# FSI6CAN.net
KiCad netlist of a schematic drawn in EAGLE
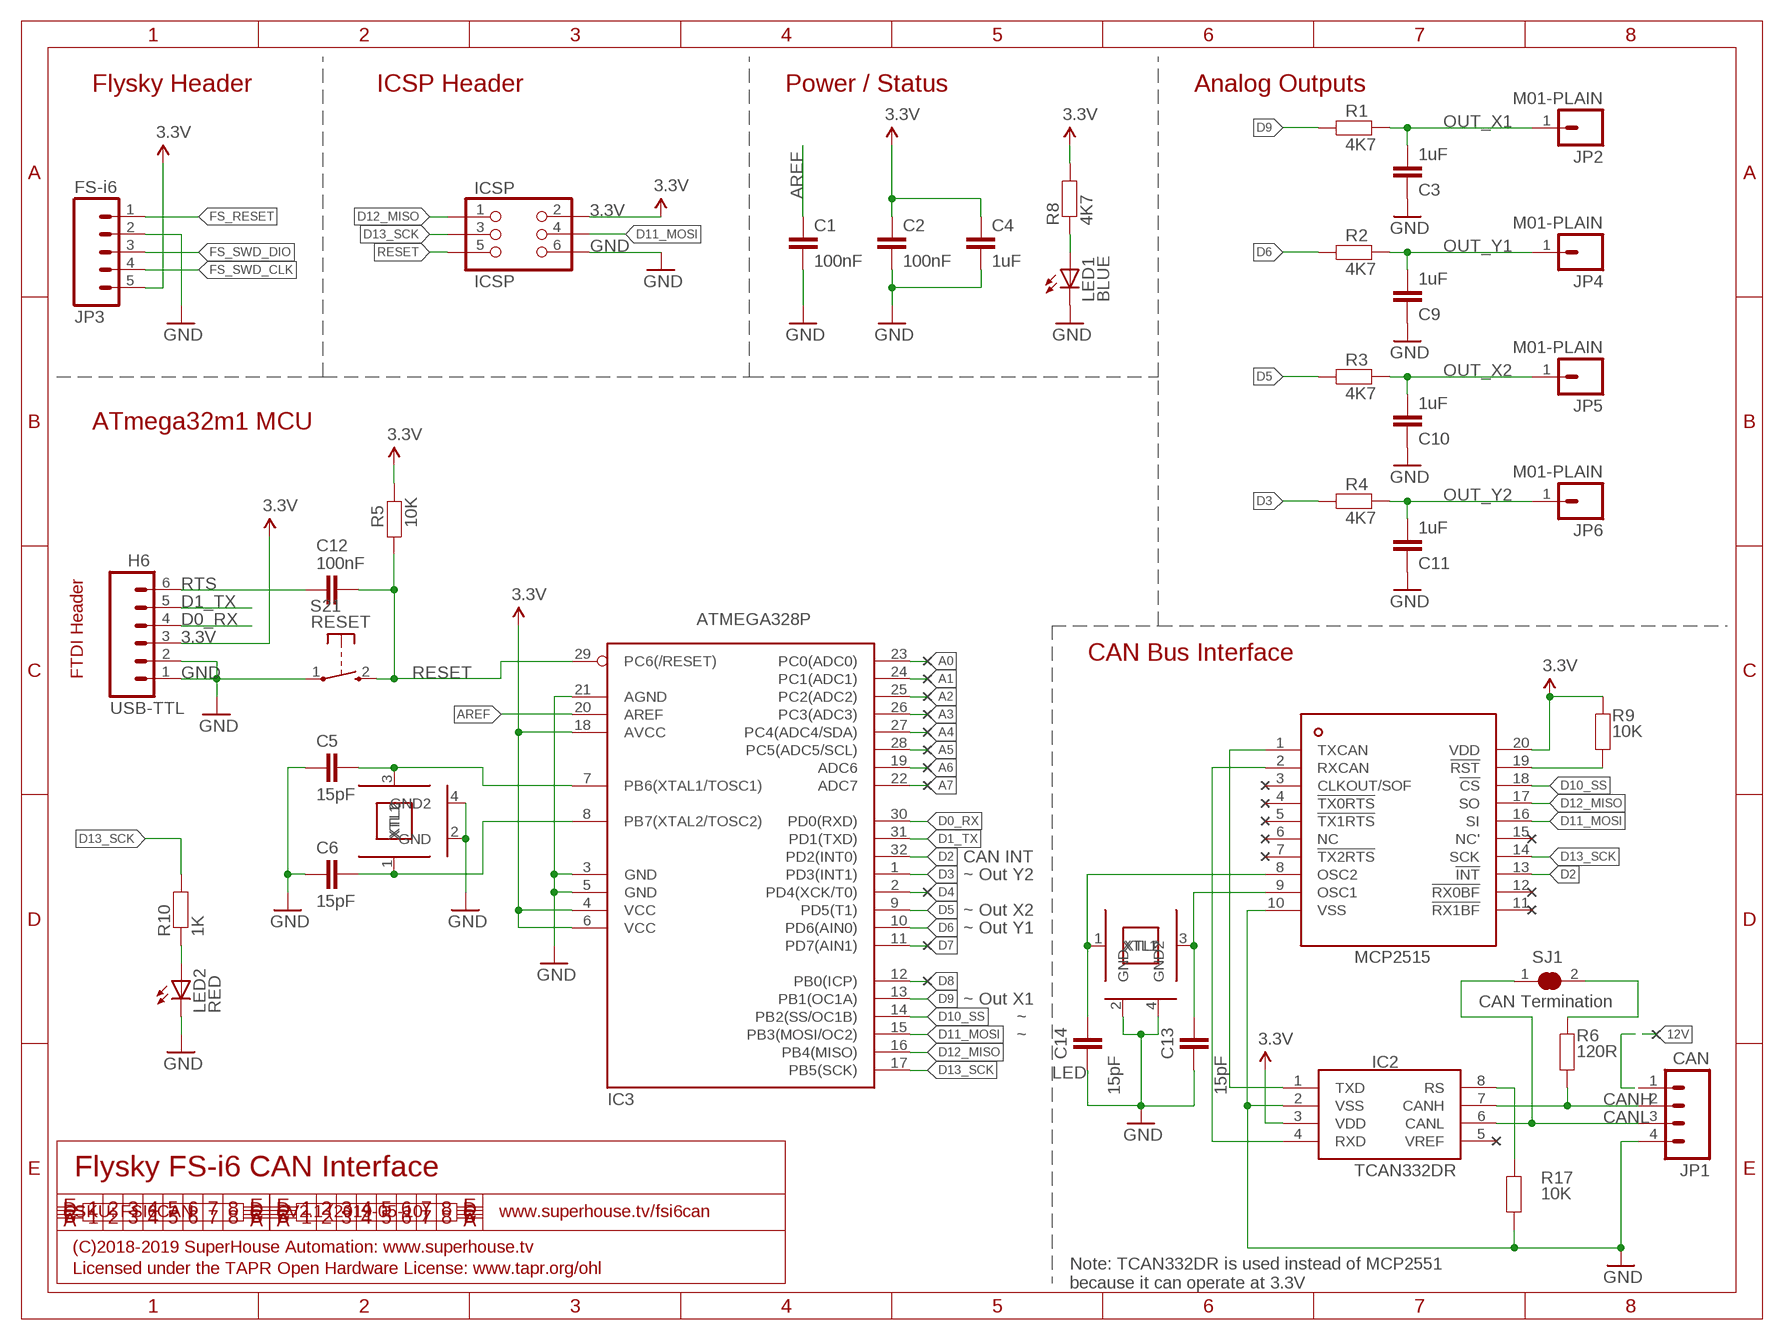
[diagram p0: schematic, sheet 1]

(export (version "E")
  (design (tool "Eeschema 10.0.6"))
  (components
    (comp (ref "C1")
      (value "100nF")
      (footprint "eagle-import:C0603")
      (libsource (lib "eagle-import") (part "CAP0603"))
    )
    (comp (ref "C2")
      (value "100nF")
      (footprint "eagle-import:C0603")
      (libsource (lib "eagle-import") (part "CAP0603"))
    )
    (comp (ref "C3")
      (value "1uF")
      (footprint "eagle-import:C0603")
      (libsource (lib "eagle-import") (part "CAP0603"))
    )
    (comp (ref "C4")
      (value "1uF")
      (footprint "eagle-import:C0603")
      (libsource (lib "eagle-import") (part "CAP0603"))
    )
    (comp (ref "C5")
      (value "15pF")
      (footprint "eagle-import:C0603")
      (libsource (lib "eagle-import") (part "CAP0603"))
    )
    (comp (ref "C6")
      (value "15pF")
      (footprint "eagle-import:C0603")
      (libsource (lib "eagle-import") (part "CAP0603"))
    )
    (comp (ref "C9")
      (value "1uF")
      (footprint "eagle-import:C0603")
      (libsource (lib "eagle-import") (part "CAP0603"))
    )
    (comp (ref "C10")
      (value "1uF")
      (footprint "eagle-import:C0603")
      (libsource (lib "eagle-import") (part "CAP0603"))
    )
    (comp (ref "C11")
      (value "1uF")
      (footprint "eagle-import:C0603")
      (libsource (lib "eagle-import") (part "CAP0603"))
    )
    (comp (ref "C12")
      (value "100nF")
      (footprint "eagle-import:C0603")
      (libsource (lib "eagle-import") (part "CAP0603"))
    )
    (comp (ref "C13")
      (value "15pF")
      (footprint "eagle-import:C0603")
      (libsource (lib "eagle-import") (part "CAP0603"))
    )
    (comp (ref "C14")
      (value "15pF")
      (footprint "eagle-import:C0603")
      (libsource (lib "eagle-import") (part "CAP0603"))
    )
    (comp (ref "H6")
      (value "USB-TTL")
      (footprint "eagle-import:1X06-P-RA")
      (libsource (lib "eagle-import") (part "M06-PIN-RIGHTANGLE"))
    )
    (comp (ref "IC2")
      (value "TCAN332DR")
      (footprint "eagle-import:SO08")
      (libsource (lib "eagle-import") (part "MCP2551"))
    )
    (comp (ref "IC3")
      (value "ATMEGA328P")
      (footprint "eagle-import:TQFP32-08")
      (libsource (lib "eagle-import") (part "ATMEGA8-AI"))
    )
    (comp (ref "IC4")
      (value "MCP2515")
      (footprint "eagle-import:TSSOP20")
      (libsource (lib "eagle-import") (part "MCP2515"))
    )
    (comp (ref "ICSP")
      (value "ICSP")
      (footprint "eagle-import:2X03-ICSP")
      (libsource (lib "eagle-import") (part "ICSP-PIN"))
    )
    (comp (ref "JP1")
      (value "CAN")
      (footprint "eagle-import:1X04-P")
      (libsource (lib "eagle-import") (part "M04-PIN"))
    )
    (comp (ref "JP2")
      (value "M01-PLAIN")
      (footprint "eagle-import:1X01")
      (libsource (lib "eagle-import") (part "M01-PLAIN"))
    )
    (comp (ref "JP3")
      (value "FS-i6")
      (footprint "eagle-import:1X05")
      (libsource (lib "eagle-import") (part "M05PTH"))
    )
    (comp (ref "JP4")
      (value "M01-PLAIN")
      (footprint "eagle-import:1X01")
      (libsource (lib "eagle-import") (part "M01-PLAIN"))
    )
    (comp (ref "JP5")
      (value "M01-PLAIN")
      (footprint "eagle-import:1X01")
      (libsource (lib "eagle-import") (part "M01-PLAIN"))
    )
    (comp (ref "JP6")
      (value "M01-PLAIN")
      (footprint "eagle-import:1X01")
      (libsource (lib "eagle-import") (part "M01-PLAIN"))
    )
    (comp (ref "LED1")
      (value "BLUE")
      (footprint "eagle-import:LED-0603")
      (libsource (lib "eagle-import") (part "LED0603"))
    )
    (comp (ref "LED2")
      (value "RED")
      (footprint "eagle-import:LED-0603")
      (libsource (lib "eagle-import") (part "LED0603"))
    )
    (comp (ref "R1")
      (value "4K7")
      (footprint "eagle-import:R0603")
      (libsource (lib "eagle-import") (part "RESISTOR0603"))
    )
    (comp (ref "R2")
      (value "4K7")
      (footprint "eagle-import:R0603")
      (libsource (lib "eagle-import") (part "RESISTOR0603"))
    )
    (comp (ref "R3")
      (value "4K7")
      (footprint "eagle-import:R0603")
      (libsource (lib "eagle-import") (part "RESISTOR0603"))
    )
    (comp (ref "R4")
      (value "4K7")
      (footprint "eagle-import:R0603")
      (libsource (lib "eagle-import") (part "RESISTOR0603"))
    )
    (comp (ref "R5")
      (value "10K")
      (footprint "eagle-import:R0603")
      (libsource (lib "eagle-import") (part "RESISTOR0603"))
    )
    (comp (ref "R6")
      (value "120R")
      (footprint "eagle-import:R0603")
      (libsource (lib "eagle-import") (part "RESISTOR0603"))
    )
    (comp (ref "R8")
      (value "4K7")
      (footprint "eagle-import:R0603")
      (libsource (lib "eagle-import") (part "RESISTOR0603"))
    )
    (comp (ref "R9")
      (value "10K")
      (footprint "eagle-import:R0603")
      (libsource (lib "eagle-import") (part "RESISTOR0603"))
    )
    (comp (ref "R10")
      (value "1K")
      (footprint "eagle-import:R0603")
      (libsource (lib "eagle-import") (part "RESISTOR0603"))
    )
    (comp (ref "R17")
      (value "10K")
      (footprint "eagle-import:R0603")
      (libsource (lib "eagle-import") (part "RESISTOR0603"))
    )
    (comp (ref "S21")
      (value "RESET")
      (footprint "eagle-import:TACTILE_SMT_3X4X2")
      (libsource (lib "eagle-import") (part "TAC_SWITCH_2PINSMT"))
    )
    (comp (ref "SJ1")
      (value "CAN Termination")
      (footprint "eagle-import:SJC")
      (libsource (lib "eagle-import") (part "SJC-NORMAL"))
    )
    (comp (ref "XTL1")
      (value "8MHz")
      (footprint "eagle-import:CRYSTAL-SMD-3X2")
      (libsource (lib "eagle-import") (part "CRYSTAL-GND3X2"))
    )
    (comp (ref "XTL3")
      (value "16MHz")
      (footprint "eagle-import:CRYSTAL-SMD-3X2")
      (libsource (lib "eagle-import") (part "CRYSTAL-GND3X2"))
    )
  )
  (nets
    (net (code "1") (name "/CANH") (class "Default")
      (node (ref "IC2") (pin "7") (pinfunction "CANH_7") (pintype "bidirectional"))
      (node (ref "JP1") (pin "2") (pinfunction "2_2") (pintype "passive"))
      (node (ref "R6") (pin "1") (pinfunction "1_1") (pintype "passive"))
    )
    (net (code "2") (name "/CANL") (class "Default")
      (node (ref "IC2") (pin "6") (pinfunction "CANL_6") (pintype "bidirectional"))
      (node (ref "JP1") (pin "3") (pinfunction "3_3") (pintype "passive"))
      (node (ref "SJ1") (pin "1") (pinfunction "1_1") (pintype "passive"))
    )
    (net (code "3") (name "/OUT_X1") (class "Default")
      (node (ref "C3") (pin "1") (pinfunction "1_1") (pintype "passive"))
      (node (ref "JP2") (pin "1") (pinfunction "1_1") (pintype "passive"))
      (node (ref "R1") (pin "2") (pinfunction "2_2") (pintype "passive"))
    )
    (net (code "4") (name "/OUT_X2") (class "Default")
      (node (ref "C10") (pin "1") (pinfunction "1_1") (pintype "passive"))
      (node (ref "JP5") (pin "1") (pinfunction "1_1") (pintype "passive"))
      (node (ref "R3") (pin "2") (pinfunction "2_2") (pintype "passive"))
    )
    (net (code "5") (name "/OUT_Y1") (class "Default")
      (node (ref "C9") (pin "1") (pinfunction "1_1") (pintype "passive"))
      (node (ref "JP4") (pin "1") (pinfunction "1_1") (pintype "passive"))
      (node (ref "R2") (pin "2") (pinfunction "2_2") (pintype "passive"))
    )
    (net (code "6") (name "/OUT_Y2") (class "Default")
      (node (ref "C11") (pin "1") (pinfunction "1_1") (pintype "passive"))
      (node (ref "JP6") (pin "1") (pinfunction "1_1") (pintype "passive"))
      (node (ref "R4") (pin "2") (pinfunction "2_2") (pintype "passive"))
    )
    (net (code "7") (name "/RTS") (class "Default")
      (node (ref "C12") (pin "1") (pinfunction "1_1") (pintype "passive"))
      (node (ref "H6") (pin "6") (pinfunction "6_6") (pintype "passive"))
    )
    (net (code "8") (name "3.3V") (class "Default")
      (node (ref "C2") (pin "1") (pinfunction "1_1") (pintype "passive"))
      (node (ref "C4") (pin "1") (pinfunction "1_1") (pintype "passive"))
      (node (ref "H6") (pin "3") (pinfunction "3_3") (pintype "passive"))
      (node (ref "IC2") (pin "3") (pinfunction "VDD_3") (pintype "bidirectional"))
      (node (ref "IC3") (pin "18") (pinfunction "AVCC_18") (pintype "bidirectional"))
      (node (ref "IC3") (pin "4") (pinfunction "VCC_4") (pintype "bidirectional"))
      (node (ref "IC3") (pin "6") (pinfunction "VCC_6") (pintype "bidirectional"))
      (node (ref "IC4") (pin "20") (pinfunction "VDD_20") (pintype "bidirectional"))
      (node (ref "ICSP") (pin "2") (pinfunction "2_2") (pintype "passive"))
      (node (ref "JP3") (pin "5") (pinfunction "5_5") (pintype "passive"))
      (node (ref "R5") (pin "1") (pinfunction "1_1") (pintype "passive"))
      (node (ref "R8") (pin "2") (pinfunction "2_2") (pintype "passive"))
      (node (ref "R9") (pin "2") (pinfunction "2_2") (pintype "passive"))
    )
    (net (code "9") (name "12V") (class "Default")
      (node (ref "JP1") (pin "1") (pinfunction "1_1") (pintype "passive"))
    )
    (net (code "10") (name "A0") (class "Default")
      (node (ref "IC3") (pin "23") (pinfunction "PC0(ADC0)_23") (pintype "bidirectional"))
    )
    (net (code "11") (name "A1") (class "Default")
      (node (ref "IC3") (pin "24") (pinfunction "PC1(ADC1)_24") (pintype "bidirectional"))
    )
    (net (code "12") (name "A2") (class "Default")
      (node (ref "IC3") (pin "25") (pinfunction "PC2(ADC2)_25") (pintype "bidirectional"))
    )
    (net (code "13") (name "A3") (class "Default")
      (node (ref "IC3") (pin "26") (pinfunction "PC3(ADC3)_26") (pintype "bidirectional"))
    )
    (net (code "14") (name "A4") (class "Default")
      (node (ref "IC3") (pin "27") (pinfunction "PC4(ADC4/SDA)_27") (pintype "bidirectional"))
    )
    (net (code "15") (name "A5") (class "Default")
      (node (ref "IC3") (pin "28") (pinfunction "PC5(ADC5/SCL)_28") (pintype "bidirectional"))
    )
    (net (code "16") (name "A6") (class "Default")
      (node (ref "IC3") (pin "19") (pinfunction "ADC6_19") (pintype "bidirectional"))
    )
    (net (code "17") (name "A7") (class "Default")
      (node (ref "IC3") (pin "22") (pinfunction "ADC7_22") (pintype "bidirectional"))
    )
    (net (code "18") (name "AREF") (class "Default")
      (node (ref "C1") (pin "1") (pinfunction "1_1") (pintype "passive"))
      (node (ref "IC3") (pin "20") (pinfunction "AREF_20") (pintype "bidirectional"))
    )
    (net (code "19") (name "D0_RX") (class "Default")
      (node (ref "H6") (pin "4") (pinfunction "4_4") (pintype "passive"))
      (node (ref "IC3") (pin "30") (pinfunction "PD0(RXD)_30") (pintype "bidirectional"))
    )
    (net (code "20") (name "D1_TX") (class "Default")
      (node (ref "H6") (pin "5") (pinfunction "5_5") (pintype "passive"))
      (node (ref "IC3") (pin "31") (pinfunction "PD1(TXD)_31") (pintype "bidirectional"))
    )
    (net (code "21") (name "D2") (class "Default")
      (node (ref "IC3") (pin "32") (pinfunction "PD2(INT0)_32") (pintype "bidirectional"))
      (node (ref "IC4") (pin "13") (pinfunction "~{INT}_13") (pintype "bidirectional"))
    )
    (net (code "22") (name "D3") (class "Default")
      (node (ref "IC3") (pin "1") (pinfunction "PD3(INT1)_1") (pintype "bidirectional"))
      (node (ref "R4") (pin "1") (pinfunction "1_1") (pintype "passive"))
    )
    (net (code "23") (name "D4") (class "Default")
      (node (ref "IC3") (pin "2") (pinfunction "PD4(XCK/T0)_2") (pintype "bidirectional"))
    )
    (net (code "24") (name "D5") (class "Default")
      (node (ref "IC3") (pin "9") (pinfunction "PD5(T1)_9") (pintype "bidirectional"))
      (node (ref "R3") (pin "1") (pinfunction "1_1") (pintype "passive"))
    )
    (net (code "25") (name "D6") (class "Default")
      (node (ref "IC3") (pin "10") (pinfunction "PD6(AIN0)_10") (pintype "bidirectional"))
      (node (ref "R2") (pin "1") (pinfunction "1_1") (pintype "passive"))
    )
    (net (code "26") (name "D7") (class "Default")
      (node (ref "IC3") (pin "11") (pinfunction "PD7(AIN1)_11") (pintype "bidirectional"))
    )
    (net (code "27") (name "D8") (class "Default")
      (node (ref "IC3") (pin "12") (pinfunction "PB0(ICP)_12") (pintype "bidirectional"))
    )
    (net (code "28") (name "D9") (class "Default")
      (node (ref "IC3") (pin "13") (pinfunction "PB1(OC1A)_13") (pintype "bidirectional"))
      (node (ref "R1") (pin "1") (pinfunction "1_1") (pintype "passive"))
    )
    (net (code "29") (name "D10_SS") (class "Default")
      (node (ref "IC3") (pin "14") (pinfunction "PB2(SS/OC1B)_14") (pintype "bidirectional"))
      (node (ref "IC4") (pin "18") (pinfunction "~{CS}_18") (pintype "bidirectional"))
    )
    (net (code "30") (name "D11_MOSI") (class "Default")
      (node (ref "IC3") (pin "15") (pinfunction "PB3(MOSI/OC2)_15") (pintype "bidirectional"))
      (node (ref "IC4") (pin "16") (pinfunction "SI_16") (pintype "bidirectional"))
      (node (ref "ICSP") (pin "4") (pinfunction "4_4") (pintype "passive"))
    )
    (net (code "31") (name "D12_MISO") (class "Default")
      (node (ref "IC3") (pin "16") (pinfunction "PB4(MISO)_16") (pintype "bidirectional"))
      (node (ref "IC4") (pin "17") (pinfunction "SO_17") (pintype "bidirectional"))
      (node (ref "ICSP") (pin "1") (pinfunction "1_1") (pintype "passive"))
    )
    (net (code "32") (name "D13_SCK") (class "Default")
      (node (ref "IC3") (pin "17") (pinfunction "PB5(SCK)_17") (pintype "bidirectional"))
      (node (ref "IC4") (pin "14") (pinfunction "SCK_14") (pintype "bidirectional"))
      (node (ref "ICSP") (pin "3") (pinfunction "3_3") (pintype "passive"))
      (node (ref "R10") (pin "2") (pinfunction "2_2") (pintype "passive"))
    )
    (net (code "33") (name "FS_RESET") (class "Default")
      (node (ref "JP3") (pin "1") (pinfunction "1_1") (pintype "passive"))
    )
    (net (code "34") (name "FS_SWD_CLK") (class "Default")
      (node (ref "JP3") (pin "4") (pinfunction "4_4") (pintype "passive"))
    )
    (net (code "35") (name "FS_SWD_DIO") (class "Default")
      (node (ref "JP3") (pin "3") (pinfunction "3_3") (pintype "passive"))
    )
    (net (code "36") (name "GND") (class "Default")
      (node (ref "C1") (pin "2") (pinfunction "2_2") (pintype "passive"))
      (node (ref "C10") (pin "2") (pinfunction "2_2") (pintype "passive"))
      (node (ref "C11") (pin "2") (pinfunction "2_2") (pintype "passive"))
      (node (ref "C13") (pin "1") (pinfunction "1_1") (pintype "passive"))
      (node (ref "C14") (pin "1") (pinfunction "1_1") (pintype "passive"))
      (node (ref "C2") (pin "2") (pinfunction "2_2") (pintype "passive"))
      (node (ref "C3") (pin "2") (pinfunction "2_2") (pintype "passive"))
      (node (ref "C4") (pin "2") (pinfunction "2_2") (pintype "passive"))
      (node (ref "C5") (pin "1") (pinfunction "1_1") (pintype "passive"))
      (node (ref "C6") (pin "1") (pinfunction "1_1") (pintype "passive"))
      (node (ref "C9") (pin "2") (pinfunction "2_2") (pintype "passive"))
      (node (ref "H6") (pin "1") (pinfunction "1_1") (pintype "passive"))
      (node (ref "H6") (pin "2") (pinfunction "2_2") (pintype "passive"))
      (node (ref "IC2") (pin "2") (pinfunction "VSS_2") (pintype "bidirectional"))
      (node (ref "IC3") (pin "21") (pinfunction "AGND_21") (pintype "bidirectional"))
      (node (ref "IC3") (pin "3") (pinfunction "GND_3") (pintype "bidirectional"))
      (node (ref "IC3") (pin "5") (pinfunction "GND_5") (pintype "bidirectional"))
      (node (ref "IC4") (pin "10") (pinfunction "VSS_10") (pintype "bidirectional"))
      (node (ref "ICSP") (pin "6") (pinfunction "6_6") (pintype "passive"))
      (node (ref "JP1") (pin "4") (pinfunction "4_4") (pintype "passive"))
      (node (ref "JP3") (pin "2") (pinfunction "2_2") (pintype "passive"))
      (node (ref "LED1") (pin "C") (pinfunction "C_C") (pintype "passive"))
      (node (ref "LED2") (pin "C") (pinfunction "C_C") (pintype "passive"))
      (node (ref "R17") (pin "1") (pinfunction "1_1") (pintype "passive"))
      (node (ref "S21") (pin "1") (pinfunction "P_1") (pintype "passive"))
      (node (ref "XTL1") (pin "2") (pinfunction "GND_2") (pintype "bidirectional"))
      (node (ref "XTL1") (pin "4") (pinfunction "GND2_4") (pintype "bidirectional"))
      (node (ref "XTL3") (pin "2") (pinfunction "GND_2") (pintype "bidirectional"))
      (node (ref "XTL3") (pin "4") (pinfunction "GND2_4") (pintype "bidirectional"))
    )
    (net (code "37") (name "Net-(IC2-RS)") (class "Default")
      (node (ref "IC2") (pin "8") (pinfunction "RS_8") (pintype "bidirectional"))
      (node (ref "R17") (pin "2") (pinfunction "2_2") (pintype "passive"))
    )
    (net (code "38") (name "Net-(IC2-RXD)") (class "Default")
      (node (ref "IC2") (pin "4") (pinfunction "RXD_4") (pintype "bidirectional"))
      (node (ref "IC4") (pin "2") (pinfunction "RXCAN_2") (pintype "bidirectional"))
    )
    (net (code "39") (name "Net-(IC2-TXD)") (class "Default")
      (node (ref "IC2") (pin "1") (pinfunction "TXD_1") (pintype "bidirectional"))
      (node (ref "IC4") (pin "1") (pinfunction "TXCAN_1") (pintype "bidirectional"))
    )
    (net (code "40") (name "Net-(IC3-PB6(XTAL1{slash}TOSC1))") (class "Default")
      (node (ref "C5") (pin "2") (pinfunction "2_2") (pintype "passive"))
      (node (ref "IC3") (pin "7") (pinfunction "PB6(XTAL1/TOSC1)_7") (pintype "bidirectional"))
      (node (ref "XTL1") (pin "3") (pinfunction "XTL2_3") (pintype "bidirectional"))
    )
    (net (code "41") (name "Net-(IC3-PB7(XTAL2{slash}TOSC2))") (class "Default")
      (node (ref "C6") (pin "2") (pinfunction "2_2") (pintype "passive"))
      (node (ref "IC3") (pin "8") (pinfunction "PB7(XTAL2/TOSC2)_8") (pintype "bidirectional"))
      (node (ref "XTL1") (pin "1") (pinfunction "XTL1_1") (pintype "bidirectional"))
    )
    (net (code "42") (name "Net-(IC4-OSC1)") (class "Default")
      (node (ref "C13") (pin "2") (pinfunction "2_2") (pintype "passive"))
      (node (ref "IC4") (pin "9") (pinfunction "OSC1_9") (pintype "bidirectional"))
      (node (ref "XTL3") (pin "3") (pinfunction "XTL2_3") (pintype "bidirectional"))
    )
    (net (code "43") (name "Net-(IC4-OSC2)") (class "Default")
      (node (ref "C14") (pin "2") (pinfunction "2_2") (pintype "passive"))
      (node (ref "IC4") (pin "8") (pinfunction "OSC2_8") (pintype "bidirectional"))
      (node (ref "XTL3") (pin "1") (pinfunction "XTL1_1") (pintype "bidirectional"))
    )
    (net (code "44") (name "Net-(IC4-~{RST})") (class "Default")
      (node (ref "IC4") (pin "19") (pinfunction "~{RST}_19") (pintype "bidirectional"))
      (node (ref "R9") (pin "1") (pinfunction "1_1") (pintype "passive"))
    )
    (net (code "45") (name "Net-(LED1-PadA)") (class "Default")
      (node (ref "LED1") (pin "A") (pinfunction "A_A") (pintype "passive"))
      (node (ref "R8") (pin "1") (pinfunction "1_1") (pintype "passive"))
    )
    (net (code "46") (name "Net-(LED2-PadA)") (class "Default")
      (node (ref "LED2") (pin "A") (pinfunction "A_A") (pintype "passive"))
      (node (ref "R10") (pin "1") (pinfunction "1_1") (pintype "passive"))
    )
    (net (code "47") (name "Net-(R6-Pad2)") (class "Default")
      (node (ref "R6") (pin "2") (pinfunction "2_2") (pintype "passive"))
      (node (ref "SJ1") (pin "2") (pinfunction "2_2") (pintype "passive"))
    )
    (net (code "48") (name "RESET") (class "Default")
      (node (ref "C12") (pin "2") (pinfunction "2_2") (pintype "passive"))
      (node (ref "IC3") (pin "29") (pinfunction "PC6(/RESET)_29") (pintype "bidirectional"))
      (node (ref "ICSP") (pin "5") (pinfunction "5_5") (pintype "passive"))
      (node (ref "R5") (pin "2") (pinfunction "2_2") (pintype "passive"))
      (node (ref "S21") (pin "2") (pinfunction "S_2") (pintype "passive"))
    )
    (net (code "49") (name "unconnected-(IC2-VREF-Pad5)") (class "Default")
      (node (ref "IC2") (pin "5") (pinfunction "VREF_5") (pintype "bidirectional"))
    )
    (net (code "50") (name "unconnected-(IC4-CLKOUT{slash}SOF-Pad3)") (class "Default")
      (node (ref "IC4") (pin "3") (pinfunction "CLKOUT/SOF_3") (pintype "bidirectional"))
    )
    (net (code "51") (name "unconnected-(IC4-NC'-Pad15)") (class "Default")
      (node (ref "IC4") (pin "15") (pinfunction "NC'_15") (pintype "bidirectional"))
    )
    (net (code "52") (name "unconnected-(IC4-NC-Pad6)") (class "Default")
      (node (ref "IC4") (pin "6") (pinfunction "NC_6") (pintype "bidirectional"))
    )
    (net (code "53") (name "unconnected-(IC4-~{RX0BF}-Pad12)") (class "Default")
      (node (ref "IC4") (pin "12") (pinfunction "~{RX0BF}_12") (pintype "bidirectional"))
    )
    (net (code "54") (name "unconnected-(IC4-~{RX1BF}-Pad11)") (class "Default")
      (node (ref "IC4") (pin "11") (pinfunction "~{RX1BF}_11") (pintype "bidirectional"))
    )
    (net (code "55") (name "unconnected-(IC4-~{TX0RTS}-Pad4)") (class "Default")
      (node (ref "IC4") (pin "4") (pinfunction "~{TX0RTS}_4") (pintype "bidirectional"))
    )
    (net (code "56") (name "unconnected-(IC4-~{TX1RTS}-Pad5)") (class "Default")
      (node (ref "IC4") (pin "5") (pinfunction "~{TX1RTS}_5") (pintype "bidirectional"))
    )
    (net (code "57") (name "unconnected-(IC4-~{TX2RTS}-Pad7)") (class "Default")
      (node (ref "IC4") (pin "7") (pinfunction "~{TX2RTS}_7") (pintype "bidirectional"))
    )
  )
)
